# 06_-_MCU.net
KiCad netlist of a schematic drawn in Altium Designer
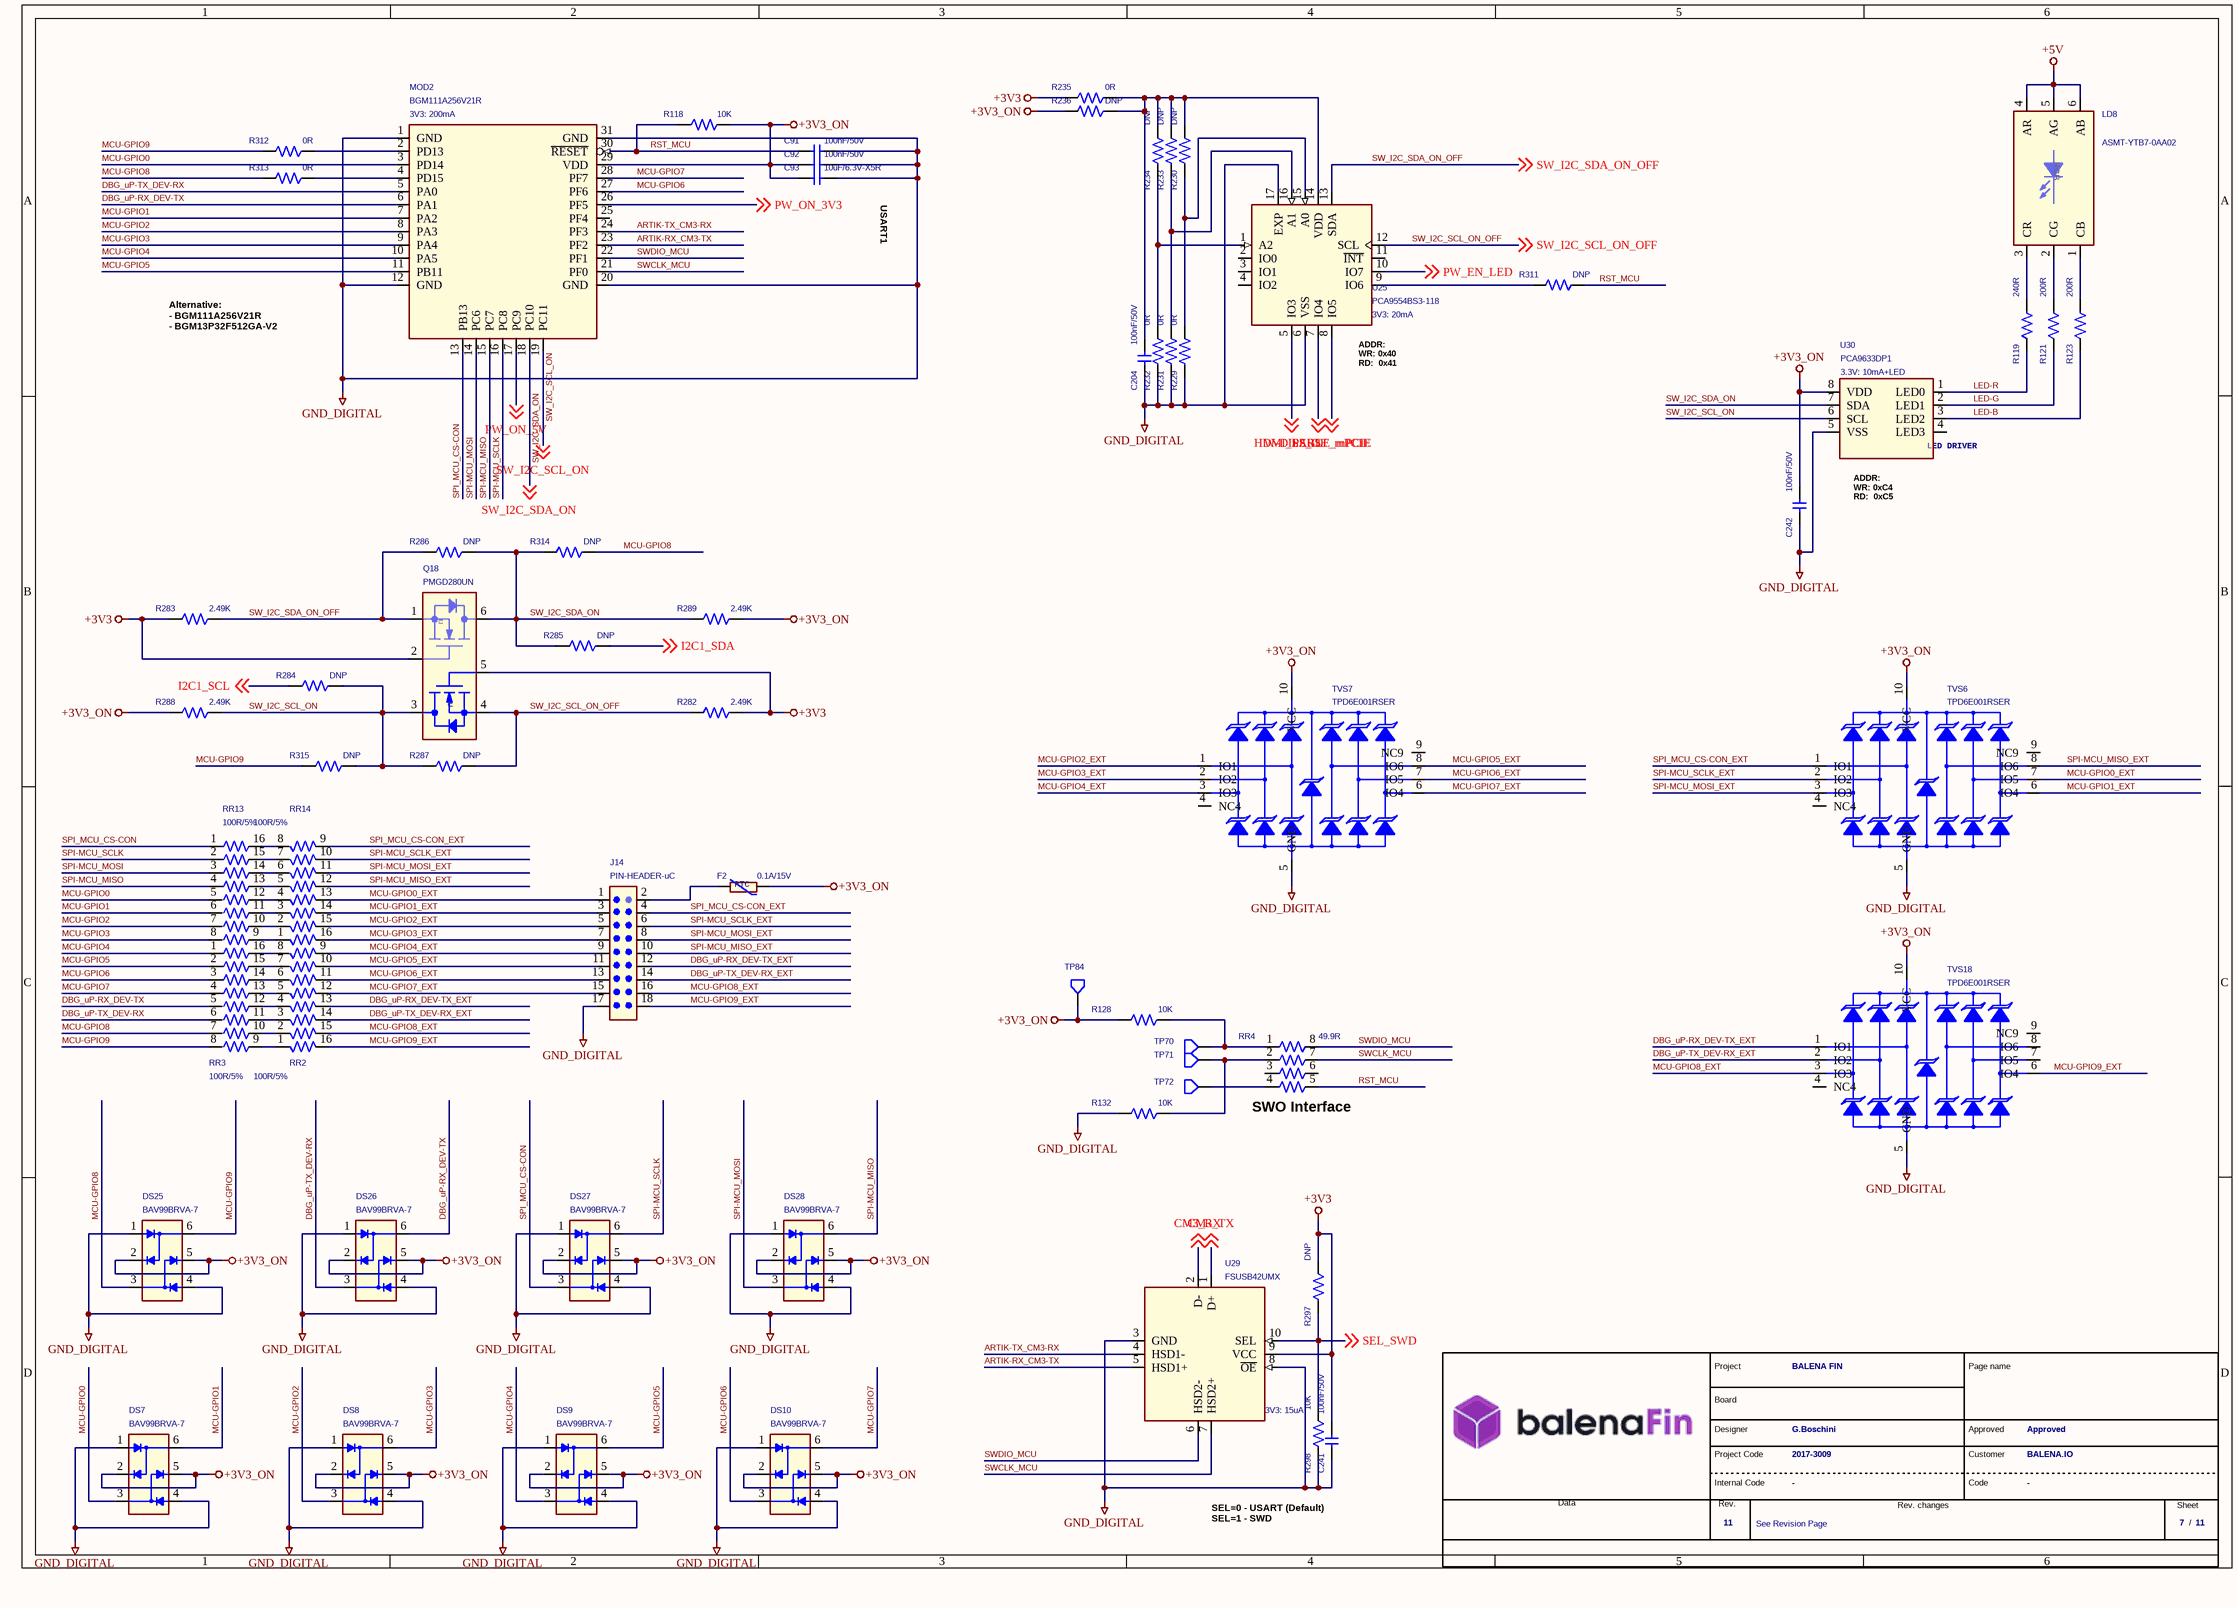
[diagram p0: 06 - MCU.SchDoc]

(export (version "E")
  (design (tool "Eeschema 10.0.6"))
  (components
    (comp (ref "C91")
      (value "100nF/50V")
      (footprint "CS-C-0402")
      (description "CHIP CAP.CER. 100nF 16V 10% X7R 0402")
      (fields (field (name "MPN") "Generic"))
      (libsource (lib "*") (part "CS-C-0402-100n/16V"))
    )
    (comp (ref "C92")
      (value "100nF/50V")
      (footprint "CS-C-0402")
      (description "CHIP CAP.CER. 100nF 16V 10% X7R 0402")
      (fields (field (name "MPN") "Generic"))
      (libsource (lib "*") (part "CS-C-0402-100n/16V"))
    )
    (comp (ref "C93")
      (value "10uF/6.3V-X5R")
      (footprint "CS-C-0402")
      (description "CHIP CAP.CER. 10uF 6.3V 20% X5R 0402")
      (fields (field (name "MPN") "Generic"))
      (libsource (lib "*") (part "CS-C-0402-10u/6V3-X5R"))
    )
    (comp (ref "C204")
      (value "100nF/50V")
      (footprint "CS-C-0402")
      (description "CHIP CAP.CER. 100nF 16V 10% X7R 0402")
      (fields (field (name "MPN") "Generic"))
      (libsource (lib "*") (part "CS-C-0402-100n/16V"))
    )
    (comp (ref "C241")
      (value "100nF/50V")
      (footprint "CS-C-0402")
      (description "CHIP CAP.CER. 100nF 16V 10% X7R 0402")
      (fields (field (name "MPN") "Generic"))
      (libsource (lib "*") (part "CS-C-0402-100n/16V"))
    )
    (comp (ref "C242")
      (value "100nF/50V")
      (footprint "CS-C-0402")
      (description "CHIP CAP.CER. 100nF 16V 10% X7R 0402")
      (fields (field (name "MPN") "Generic"))
      (libsource (lib "*") (part "CS-C-0402-100n/16V"))
    )
    (comp (ref "DS7")
      (value "BAV99BRVA-7")
      (footprint "SOT563")
      (description "Diode Switching 75V 0.215A 6-Pin SOT-563 T/R")
      (libsource (lib "*") (part "DIODO4x - BAV99BRVA-7 -0.2A/75V"))
    )
    (comp (ref "DS8")
      (value "BAV99BRVA-7")
      (footprint "SOT563")
      (description "Diode Switching 75V 0.215A 6-Pin SOT-563 T/R")
      (libsource (lib "*") (part "DIODO4x - BAV99BRVA-7 -0.2A/75V"))
    )
    (comp (ref "DS9")
      (value "BAV99BRVA-7")
      (footprint "SOT563")
      (description "Diode Switching 75V 0.215A 6-Pin SOT-563 T/R")
      (libsource (lib "*") (part "DIODO4x - BAV99BRVA-7 -0.2A/75V"))
    )
    (comp (ref "DS10")
      (value "BAV99BRVA-7")
      (footprint "SOT563")
      (description "Diode Switching 75V 0.215A 6-Pin SOT-563 T/R")
      (libsource (lib "*") (part "DIODO4x - BAV99BRVA-7 -0.2A/75V"))
    )
    (comp (ref "DS25")
      (value "BAV99BRVA-7")
      (footprint "SOT563")
      (description "Diode Switching 75V 0.215A 6-Pin SOT-563 T/R")
      (libsource (lib "*") (part "DIODO4x - BAV99BRVA-7 -0.2A/75V"))
    )
    (comp (ref "DS26")
      (value "BAV99BRVA-7")
      (footprint "SOT563")
      (description "Diode Switching 75V 0.215A 6-Pin SOT-563 T/R")
      (libsource (lib "*") (part "DIODO4x - BAV99BRVA-7 -0.2A/75V"))
    )
    (comp (ref "DS27")
      (value "BAV99BRVA-7")
      (footprint "SOT563")
      (description "Diode Switching 75V 0.215A 6-Pin SOT-563 T/R")
      (libsource (lib "*") (part "DIODO4x - BAV99BRVA-7 -0.2A/75V"))
    )
    (comp (ref "DS28")
      (value "BAV99BRVA-7")
      (footprint "SOT563")
      (description "Diode Switching 75V 0.215A 6-Pin SOT-563 T/R")
      (libsource (lib "*") (part "DIODO4x - BAV99BRVA-7 -0.2A/75V"))
    )
    (comp (ref "F2")
      (value "0.1A/15V")
      (footprint "FS-0603")
      (description "PTC RESET FUSE 15V 100MA 0603")
      (fields (field (name "MPN") "0ZCM0010FF2G"))
      (libsource (lib "*") (part "PTC - 0ZCM0010FF2G - 0.1A/15V"))
    )
    (comp (ref "J14")
      (value "PIN-HEADER-uC")
      (footprint "J-9X2-0254-MDT")
      (description "CONN HEADER THT 18POS 2.54MM DUAL ROW")
      (fields (field (name "MPN") "Generic"))
      (libsource (lib "*") (part "STRIP-J-9X2-0254-MDT"))
    )
    (comp (ref "LD8")
      (value "ASMT-YTB7-0AA02")
      (footprint "LD-PLCC6-GUIDAVLP")
      (description "LED RGB- 623nm Red, 529nm Green, PLCC6 469nm Blue LED Indication -  Discrete 2.1V Red, 3.1V")
      (libsource (lib "*") (part "LED RGB - ASMT-YTB7-0AA02"))
    )
    (comp (ref "MOD2")
      (value "BGM111A256V21R")
      (footprint "MOD-ARTIK-020")
      (description "Bluetooth v4.2 Transceiver Module 2.4GHz Integrated, Chip Surface Mount")
      (fields (field (name "POWER REQUIREMENTS") "3V3: 200mA"))
      (libsource (lib "*") (part "ARTIK - 020"))
    )
    (comp (ref "Q18")
      (value "PMGD280UN")
      (footprint "SOT363")
      (description "MOSFET 2N-CH 20V 0.87A 6TSSOP")
      (libsource (lib "*") (part "NMOS-2X - PMGD280UN - 0.87A/20V"))
    )
    (comp (ref "R118")
      (value "10K")
      (footprint "RS-0402")
      (description "CHIP RES. 10K 0402 1/16W 1%")
      (fields (field (name "MPN") "Generic"))
      (libsource (lib "*") (part "RS-0402-10k"))
    )
    (comp (ref "R119")
      (value "240R")
      (footprint "RS-0402")
      (description "CHIP RES. 240R 0402 1/16W 1% 100PPM/°C")
      (fields (field (name "MPN") "Generic"))
      (libsource (lib "*") (part "RS-0402-240r"))
    )
    (comp (ref "R121")
      (value "200R")
      (footprint "RS-0402")
      (description "CHIP RES. 200R 0402 1/16W 1% 100PPM/°C")
      (fields (field (name "MPN") "Generic"))
      (libsource (lib "*") (part "RS-0402-200r"))
    )
    (comp (ref "R123")
      (value "200R")
      (footprint "RS-0402")
      (description "CHIP RES. 200R 0402 1/16W 1% 100PPM/°C")
      (fields (field (name "MPN") "Generic"))
      (libsource (lib "*") (part "RS-0402-200r"))
    )
    (comp (ref "R128")
      (value "10K")
      (footprint "RS-0402")
      (description "CHIP RES. 10K 0402 1/16W 1%")
      (fields (field (name "MPN") "Generic"))
      (libsource (lib "*") (part "RS-0402-10k"))
    )
    (comp (ref "R132")
      (value "10K")
      (footprint "RS-0402")
      (description "CHIP RES. 10K 0402 1/16W 1%")
      (fields (field (name "MPN") "Generic"))
      (libsource (lib "*") (part "RS-0402-10k"))
    )
    (comp (ref "R229")
      (value "0R")
      (footprint "RS-0402")
      (description "CHIP RES. 0R 0402 1/16W 1%")
      (fields (field (name "MPN") "Generic"))
      (libsource (lib "*") (part "RS-0402-0r"))
    )
    (comp (ref "R230")
      (value "DNP")
      (footprint "RS-0402")
      (description "CHIP RES. 0402")
      (fields (field (name "MPN") "Generic"))
      (libsource (lib "*") (part "RS-0402"))
    )
    (comp (ref "R231")
      (value "0R")
      (footprint "RS-0402")
      (description "CHIP RES. 0R 0402 1/16W 1%")
      (fields (field (name "MPN") "Generic"))
      (libsource (lib "*") (part "RS-0402-0r"))
    )
    (comp (ref "R232")
      (value "0R")
      (footprint "RS-0402")
      (description "CHIP RES. 0R 0402 1/16W 1%")
      (fields (field (name "MPN") "Generic"))
      (libsource (lib "*") (part "RS-0402-0r"))
    )
    (comp (ref "R233")
      (value "DNP")
      (footprint "RS-0402")
      (description "CHIP RES. 0402")
      (fields (field (name "MPN") "Generic"))
      (libsource (lib "*") (part "RS-0402"))
    )
    (comp (ref "R234")
      (value "DNP")
      (footprint "RS-0402")
      (description "CHIP RES. 0402")
      (fields (field (name "MPN") "Generic"))
      (libsource (lib "*") (part "RS-0402"))
    )
    (comp (ref "R235")
      (value "0R")
      (footprint "RS-0402")
      (description "CHIP RES. 0R 0402 1/16W 1%")
      (fields (field (name "MPN") "Generic"))
      (libsource (lib "*") (part "RS-0402-0r"))
    )
    (comp (ref "R236")
      (value "DNP")
      (footprint "RS-0402")
      (description "CHIP RES. 0402")
      (fields (field (name "MPN") "Generic"))
      (libsource (lib "*") (part "RS-0402"))
    )
    (comp (ref "R282")
      (value "2.49K")
      (footprint "RS-0402")
      (description "CHIP RES. 2K49 0402 1/16W 1% 100PPM/°C")
      (fields (field (name "MPN") "Generic"))
      (libsource (lib "*") (part "RS-0402-2.49k"))
    )
    (comp (ref "R283")
      (value "2.49K")
      (footprint "RS-0402")
      (description "CHIP RES. 2K49 0402 1/16W 1% 100PPM/°C")
      (fields (field (name "MPN") "Generic"))
      (libsource (lib "*") (part "RS-0402-2.49k"))
    )
    (comp (ref "R284")
      (value "DNP")
      (footprint "RS-0402")
      (description "CHIP RES. 0402")
      (fields (field (name "MPN") "Generic"))
      (libsource (lib "*") (part "RS-0402"))
    )
    (comp (ref "R285")
      (value "DNP")
      (footprint "RS-0402")
      (description "CHIP RES. 0402")
      (fields (field (name "MPN") "Generic"))
      (libsource (lib "*") (part "RS-0402"))
    )
    (comp (ref "R286")
      (value "DNP")
      (footprint "RS-0402")
      (description "CHIP RES. 0R 0402 1/10W 1%")
      (fields (field (name "MPN") "Generic"))
      (libsource (lib "*") (part "RS-0402"))
    )
    (comp (ref "R287")
      (value "DNP")
      (footprint "RS-0402")
      (description "CHIP RES. 0R 0402 1/10W 1%")
      (fields (field (name "MPN") "Generic"))
      (libsource (lib "*") (part "RS-0402"))
    )
    (comp (ref "R288")
      (value "2.49K")
      (footprint "RS-0402")
      (description "CHIP RES. 2K49 0402 1/16W 1% 100PPM/°C")
      (fields (field (name "MPN") "Generic"))
      (libsource (lib "*") (part "RS-0402-2.49k"))
    )
    (comp (ref "R289")
      (value "2.49K")
      (footprint "RS-0402")
      (description "CHIP RES. 2K49 0402 1/16W 1% 100PPM/°C")
      (fields (field (name "MPN") "Generic"))
      (libsource (lib "*") (part "RS-0402-2.49k"))
    )
    (comp (ref "R297")
      (value "DNP")
      (footprint "RS-0402")
      (description "CHIP RES. 0402")
      (fields (field (name "MPN") "Generic"))
      (libsource (lib "*") (part "RS-0402"))
    )
    (comp (ref "R298")
      (value "10K")
      (footprint "RS-0402")
      (description "CHIP RES. 10K 0402 1/16W 1%")
      (fields (field (name "MPN") "Generic"))
      (libsource (lib "*") (part "RS-0402-10k"))
    )
    (comp (ref "R311")
      (value "DNP")
      (footprint "RS-0402")
      (description "CHIP RES. 0R 0402 1/16W 1%")
      (fields (field (name "MPN") "Generic"))
      (libsource (lib "*") (part "RS-0402-0r"))
    )
    (comp (ref "R312")
      (value "0R")
      (footprint "RS-0402")
      (description "CHIP RES. 0R 0402 1/16W 1%")
      (fields (field (name "MPN") "Generic"))
      (libsource (lib "*") (part "RS-0402-0r"))
    )
    (comp (ref "R313")
      (value "0R")
      (footprint "RS-0402")
      (description "CHIP RES. 0R 0402 1/16W 1%")
      (fields (field (name "MPN") "Generic"))
      (libsource (lib "*") (part "RS-0402-0r"))
    )
    (comp (ref "R314")
      (value "DNP")
      (footprint "RS-0402")
      (description "CHIP RES. 0402")
      (fields (field (name "MPN") "Generic"))
      (libsource (lib "*") (part "RS-0402"))
    )
    (comp (ref "R315")
      (value "DNP")
      (footprint "RS-0402")
      (description "CHIP RES. 0402")
      (fields (field (name "MPN") "Generic"))
      (libsource (lib "*") (part "RS-0402"))
    )
    (comp (ref "RR2")
      (value "100R/5%")
      (footprint "RR-8X-1506")
      (description "RES ARRAY 8 RES 100 OHM 1506 5%")
      (fields (field (name "MPN") "Generic"))
      (libsource (lib "*") (part "RR-8X-1506-100r/5%"))
    )
    (comp (ref "RR3")
      (value "100R/5%")
      (footprint "RR-8X-1506")
      (description "RES ARRAY 8 RES 100 OHM 1506 5%")
      (fields (field (name "MPN") "Generic"))
      (libsource (lib "*") (part "RR-8X-1506-100r/5%"))
    )
    (comp (ref "RR4")
      (value "49.9R")
      (footprint "RR-1206")
      (description "RES ARRAY 4 RES 49.9 OHM 1206 1%")
      (fields (field (name "MPN") "Generic"))
      (libsource (lib "*") (part "RR-1206-49.9r"))
    )
    (comp (ref "RR13")
      (value "100R/5%")
      (footprint "RR-8X-1506")
      (description "RES ARRAY 8 RES 100 OHM 1506 5%")
      (fields (field (name "MPN") "Generic"))
      (libsource (lib "*") (part "RR-8X-1506-100r/5%"))
    )
    (comp (ref "RR14")
      (value "100R/5%")
      (footprint "RR-8X-1506")
      (description "RES ARRAY 8 RES 100 OHM 1506 5%")
      (fields (field (name "MPN") "Generic"))
      (libsource (lib "*") (part "RR-8X-1506-100r/5%"))
    )
    (comp (ref "TP70")
      (value "TPS")
      (footprint "TPS-0100")
      (description "TEST POINT SMD")
      (fields (field (name "MPN") "TP-No-BoM"))
      (libsource (lib "*") (part "TEST POINT SMD 1 MM"))
    )
    (comp (ref "TP71")
      (value "TPS")
      (footprint "TPS-0100")
      (description "TEST POINT SMD")
      (fields (field (name "MPN") "TP-No-BoM"))
      (libsource (lib "*") (part "TEST POINT SMD 1 MM"))
    )
    (comp (ref "TP72")
      (value "TPS")
      (footprint "TPS-0100")
      (description "TEST POINT SMD")
      (fields (field (name "MPN") "TP-No-BoM"))
      (libsource (lib "*") (part "TEST POINT SMD 1 MM"))
    )
    (comp (ref "TP84")
      (value "TPS")
      (footprint "TPS-0100")
      (description "TEST POINT SMD")
      (fields (field (name "MPN") "TP-No-BoM"))
      (libsource (lib "*") (part "TEST POINT SMD 1 MM"))
    )
    (comp (ref "TVS6")
      (value "TPD6E001RSER")
      (footprint "UFQFN10")
      (description "TVS DIODE 5VWM")
      (libsource (lib "*") (part "TVS-UNI6x - TPD6E001RSER"))
    )
    (comp (ref "TVS7")
      (value "TPD6E001RSER")
      (footprint "UFQFN10")
      (description "TVS DIODE 5VWM")
      (libsource (lib "*") (part "TVS-UNI6x - TPD6E001RSER"))
    )
    (comp (ref "TVS18")
      (value "TPD6E001RSER")
      (footprint "UFQFN10")
      (description "TVS DIODE 5VWM")
      (libsource (lib "*") (part "TVS-UNI6x - TPD6E001RSER"))
    )
    (comp (ref "U25")
      (value "PCA9554BS3-118")
      (footprint "QFN16-EXP-3X3-4X4")
      (description "IC I/O EXPANDER I2C 8B 16HVQFN")
      (fields (field (name "POWER REQUIREMENTS") "3V3: 20mA"))
      (libsource (lib "*") (part "IO EXP-8b - PCA9554BS3-118"))
    )
    (comp (ref "U29")
      (value "FSUSB42UMX")
      (footprint "UMLP10")
      (description "USB Switch IC 1 Channel 10-UMLP (1.8x1.4)")
      (fields (field (name "POWER REQUIREMENTS") "3V3: 15uA"))
      (libsource (lib "*") (part "SWITCH-USB - FSUSB42UMX"))
    )
    (comp (ref "U30")
      (value "PCA9633DP1")
      (footprint "MSOP8")
      (description "IC LED DRIVER PS DIM 25MA 8TSSOP")
      (fields (field (name "POWER REQUIREMENTS") "3.3V: 10mA+LED"))
      (libsource (lib "*") (part "LED DRIVER-4x - PCA9633DP1"))
    )
  )
  (nets
    (net (code "1") (name "+3V3") (class "Default")
      (node (ref "C241") (pin "1") (pinfunction "1_1") (pintype "passive"))
      (node (ref "Q18") (pin "2") (pinfunction "G1_2") (pintype "passive"))
      (node (ref "Q18") (pin "5") (pinfunction "G2_5") (pintype "passive"))
      (node (ref "R235") (pin "2") (pinfunction "2_2") (pintype "passive"))
      (node (ref "R282") (pin "1") (pinfunction "1_1") (pintype "passive"))
      (node (ref "R283") (pin "2") (pinfunction "2_2") (pintype "passive"))
      (node (ref "R297") (pin "2") (pinfunction "2_2") (pintype "passive"))
      (node (ref "U29") (pin "9") (pinfunction "VCC_9") (pintype "power_in"))
    )
    (net (code "2") (name "+3V3_ON") (class "Default")
      (node (ref "C242") (pin "1") (pinfunction "1_1") (pintype "passive"))
      (node (ref "C92") (pin "1") (pinfunction "1_1") (pintype "passive"))
      (node (ref "C93") (pin "1") (pinfunction "1_1") (pintype "passive"))
      (node (ref "DS10") (pin "2") (pinfunction "C1_2") (pintype "passive"))
      (node (ref "DS10") (pin "5") (pinfunction "C2_5") (pintype "passive"))
      (node (ref "DS25") (pin "2") (pinfunction "C1_2") (pintype "passive"))
      (node (ref "DS25") (pin "5") (pinfunction "C2_5") (pintype "passive"))
      (node (ref "DS26") (pin "2") (pinfunction "C1_2") (pintype "passive"))
      (node (ref "DS26") (pin "5") (pinfunction "C2_5") (pintype "passive"))
      (node (ref "DS27") (pin "2") (pinfunction "C1_2") (pintype "passive"))
      (node (ref "DS27") (pin "5") (pinfunction "C2_5") (pintype "passive"))
      (node (ref "DS28") (pin "2") (pinfunction "C1_2") (pintype "passive"))
      (node (ref "DS28") (pin "5") (pinfunction "C2_5") (pintype "passive"))
      (node (ref "DS7") (pin "2") (pinfunction "C1_2") (pintype "passive"))
      (node (ref "DS7") (pin "5") (pinfunction "C2_5") (pintype "passive"))
      (node (ref "DS8") (pin "2") (pinfunction "C1_2") (pintype "passive"))
      (node (ref "DS8") (pin "5") (pinfunction "C2_5") (pintype "passive"))
      (node (ref "DS9") (pin "2") (pinfunction "C1_2") (pintype "passive"))
      (node (ref "DS9") (pin "5") (pinfunction "C2_5") (pintype "passive"))
      (node (ref "F2") (pin "2") (pinfunction "2_2") (pintype "passive"))
      (node (ref "MOD2") (pin "29") (pinfunction "VDD_29") (pintype "power_in"))
      (node (ref "R118") (pin "2") (pinfunction "2_2") (pintype "passive"))
      (node (ref "R128") (pin "2") (pinfunction "2_2") (pintype "passive"))
      (node (ref "R236") (pin "2") (pinfunction "2_2") (pintype "passive"))
      (node (ref "R288") (pin "2") (pinfunction "2_2") (pintype "passive"))
      (node (ref "R289") (pin "1") (pinfunction "1_1") (pintype "passive"))
      (node (ref "TP84") (pin "1") (pinfunction "TP_1") (pintype "passive"))
      (node (ref "TVS18") (pin "10") (pinfunction "VCC_10") (pintype "passive"))
      (node (ref "TVS6") (pin "10") (pinfunction "VCC_10") (pintype "passive"))
      (node (ref "TVS7") (pin "10") (pinfunction "VCC_10") (pintype "passive"))
      (node (ref "U30") (pin "8") (pinfunction "VDD_8") (pintype "power_in"))
    )
    (net (code "3") (name "+5V") (class "Default")
      (node (ref "LD8") (pin "4") (pinfunction "AR_4") (pintype "passive"))
      (node (ref "LD8") (pin "5") (pinfunction "AG_5") (pintype "passive"))
      (node (ref "LD8") (pin "6") (pinfunction "AB_6") (pintype "passive"))
    )
    (net (code "4") (name "/ARTIK-RX_CM3-TX") (class "Default")
      (node (ref "MOD2") (pin "23") (pinfunction "PF2_23") (pintype "bidirectional"))
      (node (ref "U29") (pin "5") (pinfunction "HSD1+_5") (pintype "bidirectional"))
    )
    (net (code "5") (name "/ARTIK-TX_CM3-RX") (class "Default")
      (node (ref "MOD2") (pin "24") (pinfunction "PF3_24") (pintype "bidirectional"))
      (node (ref "U29") (pin "4") (pinfunction "HSD1-_4") (pintype "bidirectional"))
    )
    (net (code "6") (name "/DBG_uP-RX_DEV-TX") (class "Default")
      (node (ref "DS26") (pin "6") (pinfunction "AC1_6") (pintype "passive"))
      (node (ref "MOD2") (pin "6") (pinfunction "PA1_6") (pintype "bidirectional"))
      (node (ref "RR3") (pin "5") (pinfunction "5_5") (pintype "passive"))
    )
    (net (code "7") (name "/DBG_uP-RX_DEV-TX_EXT") (class "Default")
      (node (ref "J14") (pin "12") (pinfunction "12_12") (pintype "passive"))
      (node (ref "RR2") (pin "13") (pinfunction "13_13") (pintype "passive"))
      (node (ref "TVS18") (pin "1") (pinfunction "IO1_1") (pintype "passive"))
    )
    (net (code "8") (name "/DBG_uP-TX_DEV-RX") (class "Default")
      (node (ref "DS26") (pin "3") (pinfunction "AC2_3") (pintype "passive"))
      (node (ref "MOD2") (pin "5") (pinfunction "PA0_5") (pintype "bidirectional"))
      (node (ref "RR3") (pin "6") (pinfunction "6_6") (pintype "passive"))
    )
    (net (code "9") (name "/DBG_uP-TX_DEV-RX_EXT") (class "Default")
      (node (ref "J14") (pin "14") (pinfunction "14_14") (pintype "passive"))
      (node (ref "RR2") (pin "14") (pinfunction "14_14") (pintype "passive"))
      (node (ref "TVS18") (pin "2") (pinfunction "IO2_2") (pintype "passive"))
    )
    (net (code "10") (name "/LED-B") (class "Default")
      (node (ref "R123") (pin "2") (pinfunction "2_2") (pintype "passive"))
      (node (ref "U30") (pin "3") (pinfunction "LED2_3") (pintype "open_collector"))
    )
    (net (code "11") (name "/LED-G") (class "Default")
      (node (ref "R121") (pin "2") (pinfunction "2_2") (pintype "passive"))
      (node (ref "U30") (pin "2") (pinfunction "LED1_2") (pintype "open_collector"))
    )
    (net (code "12") (name "/LED-R") (class "Default")
      (node (ref "R119") (pin "2") (pinfunction "2_2") (pintype "passive"))
      (node (ref "U30") (pin "1") (pinfunction "LED0_1") (pintype "open_collector"))
    )
    (net (code "13") (name "/MCU-GPIO0") (class "Default")
      (node (ref "DS7") (pin "3") (pinfunction "AC2_3") (pintype "passive"))
      (node (ref "MOD2") (pin "3") (pinfunction "PD14_3") (pintype "bidirectional"))
      (node (ref "RR13") (pin "5") (pinfunction "5_5") (pintype "passive"))
    )
    (net (code "14") (name "/MCU-GPIO0_EXT") (class "Default")
      (node (ref "J14") (pin "1") (pinfunction "1_1") (pintype "passive"))
      (node (ref "RR14") (pin "13") (pinfunction "13_13") (pintype "passive"))
      (node (ref "TVS6") (pin "7") (pinfunction "IO5_7") (pintype "passive"))
    )
    (net (code "15") (name "/MCU-GPIO1") (class "Default")
      (node (ref "DS7") (pin "6") (pinfunction "AC1_6") (pintype "passive"))
      (node (ref "MOD2") (pin "7") (pinfunction "PA2_7") (pintype "bidirectional"))
      (node (ref "RR13") (pin "6") (pinfunction "6_6") (pintype "passive"))
    )
    (net (code "16") (name "/MCU-GPIO1_EXT") (class "Default")
      (node (ref "J14") (pin "3") (pinfunction "3_3") (pintype "passive"))
      (node (ref "RR14") (pin "14") (pinfunction "14_14") (pintype "passive"))
      (node (ref "TVS6") (pin "6") (pinfunction "IO4_6") (pintype "passive"))
    )
    (net (code "17") (name "/MCU-GPIO2") (class "Default")
      (node (ref "DS8") (pin "3") (pinfunction "AC2_3") (pintype "passive"))
      (node (ref "MOD2") (pin "8") (pinfunction "PA3_8") (pintype "bidirectional"))
      (node (ref "RR13") (pin "7") (pinfunction "7_7") (pintype "passive"))
    )
    (net (code "18") (name "/MCU-GPIO2_EXT") (class "Default")
      (node (ref "J14") (pin "5") (pinfunction "5_5") (pintype "passive"))
      (node (ref "RR14") (pin "15") (pinfunction "15_15") (pintype "passive"))
      (node (ref "TVS7") (pin "1") (pinfunction "IO1_1") (pintype "passive"))
    )
    (net (code "19") (name "/MCU-GPIO3") (class "Default")
      (node (ref "DS8") (pin "6") (pinfunction "AC1_6") (pintype "passive"))
      (node (ref "MOD2") (pin "9") (pinfunction "PA4_9") (pintype "bidirectional"))
      (node (ref "RR13") (pin "8") (pinfunction "8_8") (pintype "passive"))
    )
    (net (code "20") (name "/MCU-GPIO3_EXT") (class "Default")
      (node (ref "J14") (pin "7") (pinfunction "7_7") (pintype "passive"))
      (node (ref "RR14") (pin "16") (pinfunction "16_16") (pintype "passive"))
      (node (ref "TVS7") (pin "2") (pinfunction "IO2_2") (pintype "passive"))
    )
    (net (code "21") (name "/MCU-GPIO4") (class "Default")
      (node (ref "DS9") (pin "3") (pinfunction "AC2_3") (pintype "passive"))
      (node (ref "MOD2") (pin "10") (pinfunction "PA5_10") (pintype "bidirectional"))
      (node (ref "RR3") (pin "1") (pinfunction "1_1") (pintype "passive"))
    )
    (net (code "22") (name "/MCU-GPIO4_EXT") (class "Default")
      (node (ref "J14") (pin "9") (pinfunction "9_9") (pintype "passive"))
      (node (ref "RR2") (pin "9") (pinfunction "9_9") (pintype "passive"))
      (node (ref "TVS7") (pin "3") (pinfunction "IO3_3") (pintype "passive"))
    )
    (net (code "23") (name "/MCU-GPIO5") (class "Default")
      (node (ref "DS9") (pin "6") (pinfunction "AC1_6") (pintype "passive"))
      (node (ref "MOD2") (pin "11") (pinfunction "PB11_11") (pintype "bidirectional"))
      (node (ref "RR3") (pin "2") (pinfunction "2_2") (pintype "passive"))
    )
    (net (code "24") (name "/MCU-GPIO5_EXT") (class "Default")
      (node (ref "J14") (pin "11") (pinfunction "11_11") (pintype "passive"))
      (node (ref "RR2") (pin "10") (pinfunction "10_10") (pintype "passive"))
      (node (ref "TVS7") (pin "8") (pinfunction "IO6_8") (pintype "passive"))
    )
    (net (code "25") (name "/MCU-GPIO6") (class "Default")
      (node (ref "DS10") (pin "3") (pinfunction "AC2_3") (pintype "passive"))
      (node (ref "MOD2") (pin "27") (pinfunction "PF6_27") (pintype "bidirectional"))
      (node (ref "RR3") (pin "3") (pinfunction "3_3") (pintype "passive"))
    )
    (net (code "26") (name "/MCU-GPIO6_EXT") (class "Default")
      (node (ref "J14") (pin "13") (pinfunction "13_13") (pintype "passive"))
      (node (ref "RR2") (pin "11") (pinfunction "11_11") (pintype "passive"))
      (node (ref "TVS7") (pin "7") (pinfunction "IO5_7") (pintype "passive"))
    )
    (net (code "27") (name "/MCU-GPIO7") (class "Default")
      (node (ref "DS10") (pin "6") (pinfunction "AC1_6") (pintype "passive"))
      (node (ref "MOD2") (pin "28") (pinfunction "PF7_28") (pintype "bidirectional"))
      (node (ref "RR3") (pin "4") (pinfunction "4_4") (pintype "passive"))
    )
    (net (code "28") (name "/MCU-GPIO7_EXT") (class "Default")
      (node (ref "J14") (pin "15") (pinfunction "15_15") (pintype "passive"))
      (node (ref "RR2") (pin "12") (pinfunction "12_12") (pintype "passive"))
      (node (ref "TVS7") (pin "6") (pinfunction "IO4_6") (pintype "passive"))
    )
    (net (code "29") (name "/MCU-GPIO8") (class "Default")
      (node (ref "DS25") (pin "3") (pinfunction "AC2_3") (pintype "passive"))
      (node (ref "R313") (pin "2") (pinfunction "2_2") (pintype "passive"))
      (node (ref "R314") (pin "1") (pinfunction "1_1") (pintype "passive"))
      (node (ref "RR3") (pin "7") (pinfunction "7_7") (pintype "passive"))
    )
    (net (code "30") (name "/MCU-GPIO8_EXT") (class "Default")
      (node (ref "J14") (pin "16") (pinfunction "16_16") (pintype "passive"))
      (node (ref "RR2") (pin "15") (pinfunction "15_15") (pintype "passive"))
      (node (ref "TVS18") (pin "3") (pinfunction "IO3_3") (pintype "passive"))
    )
    (net (code "31") (name "/MCU-GPIO9") (class "Default")
      (node (ref "DS25") (pin "6") (pinfunction "AC1_6") (pintype "passive"))
      (node (ref "R312") (pin "2") (pinfunction "2_2") (pintype "passive"))
      (node (ref "R315") (pin "2") (pinfunction "2_2") (pintype "passive"))
      (node (ref "RR3") (pin "8") (pinfunction "8_8") (pintype "passive"))
    )
    (net (code "32") (name "/MCU-GPIO9_EXT") (class "Default")
      (node (ref "J14") (pin "18") (pinfunction "18_18") (pintype "passive"))
      (node (ref "RR2") (pin "16") (pinfunction "16_16") (pintype "passive"))
      (node (ref "TVS18") (pin "6") (pinfunction "IO4_6") (pintype "passive"))
    )
    (net (code "33") (name "/RST_MCU") (class "Default")
      (node (ref "C91") (pin "1") (pinfunction "1_1") (pintype "passive"))
      (node (ref "MOD2") (pin "30") (pinfunction "~{RESET}_30") (pintype "input"))
      (node (ref "R118") (pin "1") (pinfunction "1_1") (pintype "passive"))
      (node (ref "R311") (pin "1") (pinfunction "1_1") (pintype "passive"))
      (node (ref "RR4") (pin "5") (pinfunction "5_5") (pintype "passive"))
    )
    (net (code "34") (name "/SPI-MCU_MISO") (class "Default")
      (node (ref "DS28") (pin "6") (pinfunction "AC1_6") (pintype "passive"))
      (node (ref "MOD2") (pin "15") (pinfunction "PC7_15") (pintype "bidirectional"))
      (node (ref "RR13") (pin "4") (pinfunction "4_4") (pintype "passive"))
    )
    (net (code "35") (name "/SPI-MCU_MISO_EXT") (class "Default")
      (node (ref "J14") (pin "10") (pinfunction "10_10") (pintype "passive"))
      (node (ref "RR14") (pin "12") (pinfunction "12_12") (pintype "passive"))
      (node (ref "TVS6") (pin "8") (pinfunction "IO6_8") (pintype "passive"))
    )
    (net (code "36") (name "/SPI-MCU_MOSI") (class "Default")
      (node (ref "DS28") (pin "3") (pinfunction "AC2_3") (pintype "passive"))
      (node (ref "MOD2") (pin "14") (pinfunction "PC6_14") (pintype "bidirectional"))
      (node (ref "RR13") (pin "3") (pinfunction "3_3") (pintype "passive"))
    )
    (net (code "37") (name "/SPI-MCU_MOSI_EXT") (class "Default")
      (node (ref "J14") (pin "8") (pinfunction "8_8") (pintype "passive"))
      (node (ref "RR14") (pin "11") (pinfunction "11_11") (pintype "passive"))
      (node (ref "TVS6") (pin "3") (pinfunction "IO3_3") (pintype "passive"))
    )
    (net (code "38") (name "/SPI-MCU_SCLK") (class "Default")
      (node (ref "DS27") (pin "6") (pinfunction "AC1_6") (pintype "passive"))
      (node (ref "MOD2") (pin "16") (pinfunction "PC8_16") (pintype "bidirectional"))
      (node (ref "RR13") (pin "2") (pinfunction "2_2") (pintype "passive"))
    )
    (net (code "39") (name "/SPI-MCU_SCLK_EXT") (class "Default")
      (node (ref "J14") (pin "6") (pinfunction "6_6") (pintype "passive"))
      (node (ref "RR14") (pin "10") (pinfunction "10_10") (pintype "passive"))
      (node (ref "TVS6") (pin "2") (pinfunction "IO2_2") (pintype "passive"))
    )
    (net (code "40") (name "/SPI_MCU_CS-CON") (class "Default")
      (node (ref "DS27") (pin "3") (pinfunction "AC2_3") (pintype "passive"))
      (node (ref "MOD2") (pin "13") (pinfunction "PB13_13") (pintype "bidirectional"))
      (node (ref "RR13") (pin "1") (pinfunction "1_1") (pintype "passive"))
    )
    (net (code "41") (name "/SPI_MCU_CS-CON_EXT") (class "Default")
      (node (ref "J14") (pin "4") (pinfunction "4_4") (pintype "passive"))
      (node (ref "RR14") (pin "9") (pinfunction "9_9") (pintype "passive"))
      (node (ref "TVS6") (pin "1") (pinfunction "IO1_1") (pintype "passive"))
    )
    (net (code "42") (name "/SWCLK_MCU") (class "Default")
      (node (ref "MOD2") (pin "21") (pinfunction "PF0_21") (pintype "bidirectional"))
      (node (ref "RR4") (pin "7") (pinfunction "7_7") (pintype "passive"))
      (node (ref "U29") (pin "7") (pinfunction "HSD2+_7") (pintype "bidirectional"))
    )
    (net (code "43") (name "/SWDIO_MCU") (class "Default")
      (node (ref "MOD2") (pin "22") (pinfunction "PF1_22") (pintype "bidirectional"))
      (node (ref "RR4") (pin "8") (pinfunction "8_8") (pintype "passive"))
      (node (ref "U29") (pin "6") (pinfunction "HSD2-_6") (pintype "bidirectional"))
    )
    (net (code "44") (name "CM3_RX") (class "Default")
      (node (ref "U29") (pin "2") (pinfunction "D-_2") (pintype "bidirectional"))
    )
    (net (code "45") (name "CM3_TX") (class "Default")
      (node (ref "U29") (pin "1") (pinfunction "D+_1") (pintype "bidirectional"))
    )
    (net (code "46") (name "GND_DIGITAL") (class "Default")
      (node (ref "C204") (pin "2") (pinfunction "2_2") (pintype "passive"))
      (node (ref "C241") (pin "2") (pinfunction "2_2") (pintype "passive"))
      (node (ref "C242") (pin "2") (pinfunction "2_2") (pintype "passive"))
      (node (ref "C91") (pin "2") (pinfunction "2_2") (pintype "passive"))
      (node (ref "C92") (pin "2") (pinfunction "2_2") (pintype "passive"))
      (node (ref "C93") (pin "2") (pinfunction "2_2") (pintype "passive"))
      (node (ref "DS10") (pin "1") (pinfunction "A1_1") (pintype "passive"))
      (node (ref "DS10") (pin "4") (pinfunction "A2_4") (pintype "passive"))
      (node (ref "DS25") (pin "1") (pinfunction "A1_1") (pintype "passive"))
      (node (ref "DS25") (pin "4") (pinfunction "A2_4") (pintype "passive"))
      (node (ref "DS26") (pin "1") (pinfunction "A1_1") (pintype "passive"))
      (node (ref "DS26") (pin "4") (pinfunction "A2_4") (pintype "passive"))
      (node (ref "DS27") (pin "1") (pinfunction "A1_1") (pintype "passive"))
      (node (ref "DS27") (pin "4") (pinfunction "A2_4") (pintype "passive"))
      (node (ref "DS28") (pin "1") (pinfunction "A1_1") (pintype "passive"))
      (node (ref "DS28") (pin "4") (pinfunction "A2_4") (pintype "passive"))
      (node (ref "DS7") (pin "1") (pinfunction "A1_1") (pintype "passive"))
      (node (ref "DS7") (pin "4") (pinfunction "A2_4") (pintype "passive"))
      (node (ref "DS8") (pin "1") (pinfunction "A1_1") (pintype "passive"))
      (node (ref "DS8") (pin "4") (pinfunction "A2_4") (pintype "passive"))
      (node (ref "DS9") (pin "1") (pinfunction "A1_1") (pintype "passive"))
      (node (ref "DS9") (pin "4") (pinfunction "A2_4") (pintype "passive"))
      (node (ref "J14") (pin "17") (pinfunction "17_17") (pintype "passive"))
      (node (ref "MOD2") (pin "1") (pinfunction "GND_1") (pintype "power_in"))
      (node (ref "MOD2") (pin "12") (pinfunction "GND_12") (pintype "power_in"))
      (node (ref "MOD2") (pin "20") (pinfunction "GND_20") (pintype "power_in"))
      (node (ref "MOD2") (pin "31") (pinfunction "GND_31") (pintype "power_in"))
      (node (ref "R132") (pin "2") (pinfunction "2_2") (pintype "passive"))
      (node (ref "R229") (pin "1") (pinfunction "1_1") (pintype "passive"))
      (node (ref "R231") (pin "1") (pinfunction "1_1") (pintype "passive"))
      (node (ref "R232") (pin "1") (pinfunction "1_1") (pintype "passive"))
      (node (ref "R298") (pin "1") (pinfunction "1_1") (pintype "passive"))
      (node (ref "TVS18") (pin "5") (pinfunction "GND_5") (pintype "power_in"))
      (node (ref "TVS6") (pin "5") (pinfunction "GND_5") (pintype "power_in"))
      (node (ref "TVS7") (pin "5") (pinfunction "GND_5") (pintype "power_in"))
      (node (ref "U25") (pin "17") (pinfunction "EXP_17") (pintype "power_in"))
      (node (ref "U25") (pin "6") (pinfunction "VSS_6") (pintype "power_in"))
      (node (ref "U29") (pin "3") (pinfunction "GND_3") (pintype "power_in"))
      (node (ref "U29") (pin "8") (pinfunction "~{OE}_8") (pintype "input"))
      (node (ref "U30") (pin "5") (pinfunction "VSS_5") (pintype "power_in"))
    )
    (net (code "47") (name "HDMI_LS_OE") (class "Default")
      (node (ref "U25") (pin "5") (pinfunction "IO3_5") (pintype "bidirectional"))
    )
    (net (code "48") (name "I2C1_SCL") (class "Default")
      (node (ref "R284") (pin "2") (pinfunction "2_2") (pintype "passive"))
    )
    (net (code "49") (name "I2C1_SDA") (class "Default")
      (node (ref "R285") (pin "1") (pinfunction "1_1") (pintype "passive"))
    )
    (net (code "50") (name "Net-(F2-Pad1)") (class "Default")
      (node (ref "F2") (pin "1") (pinfunction "1_1") (pintype "passive"))
      (node (ref "J14") (pin "2") (pinfunction "2_2") (pintype "passive"))
    )
    (net (code "51") (name "Net-(LD8-CB)") (class "Default")
      (node (ref "LD8") (pin "1") (pinfunction "CB_1") (pintype "passive"))
      (node (ref "R123") (pin "1") (pinfunction "1_1") (pintype "passive"))
    )
    (net (code "52") (name "Net-(LD8-CG)") (class "Default")
      (node (ref "LD8") (pin "2") (pinfunction "CG_2") (pintype "passive"))
      (node (ref "R121") (pin "1") (pinfunction "1_1") (pintype "passive"))
    )
    (net (code "53") (name "Net-(LD8-CR)") (class "Default")
      (node (ref "LD8") (pin "3") (pinfunction "CR_3") (pintype "passive"))
      (node (ref "R119") (pin "1") (pinfunction "1_1") (pintype "passive"))
    )
    (net (code "54") (name "Net-(MOD2-PD13)") (class "Default")
      (node (ref "MOD2") (pin "2") (pinfunction "PD13_2") (pintype "bidirectional"))
      (node (ref "R312") (pin "1") (pinfunction "1_1") (pintype "passive"))
    )
    (net (code "55") (name "Net-(MOD2-PD15)") (class "Default")
      (node (ref "MOD2") (pin "4") (pinfunction "PD15_4") (pintype "bidirectional"))
      (node (ref "R313") (pin "1") (pinfunction "1_1") (pintype "passive"))
    )
    (net (code "56") (name "Net-(RR2-Pad1)") (class "Default")
      (node (ref "RR2") (pin "1") (pinfunction "1_1") (pintype "passive"))
      (node (ref "RR3") (pin "9") (pinfunction "9_9") (pintype "passive"))
    )
    (net (code "57") (name "Net-(RR2-Pad2)") (class "Default")
      (node (ref "RR2") (pin "2") (pinfunction "2_2") (pintype "passive"))
      (node (ref "RR3") (pin "10") (pinfunction "10_10") (pintype "passive"))
    )
    (net (code "58") (name "Net-(RR2-Pad3)") (class "Default")
      (node (ref "RR2") (pin "3") (pinfunction "3_3") (pintype "passive"))
      (node (ref "RR3") (pin "11") (pinfunction "11_11") (pintype "passive"))
    )
    (net (code "59") (name "Net-(RR2-Pad4)") (class "Default")
      (node (ref "RR2") (pin "4") (pinfunction "4_4") (pintype "passive"))
      (node (ref "RR3") (pin "12") (pinfunction "12_12") (pintype "passive"))
    )
    (net (code "60") (name "Net-(RR2-Pad5)") (class "Default")
      (node (ref "RR2") (pin "5") (pinfunction "5_5") (pintype "passive"))
      (node (ref "RR3") (pin "13") (pinfunction "13_13") (pintype "passive"))
    )
    (net (code "61") (name "Net-(RR2-Pad6)") (class "Default")
      (node (ref "RR2") (pin "6") (pinfunction "6_6") (pintype "passive"))
      (node (ref "RR3") (pin "14") (pinfunction "14_14") (pintype "passive"))
    )
    (net (code "62") (name "Net-(RR2-Pad7)") (class "Default")
      (node (ref "RR2") (pin "7") (pinfunction "7_7") (pintype "passive"))
      (node (ref "RR3") (pin "15") (pinfunction "15_15") (pintype "passive"))
    )
    (net (code "63") (name "Net-(RR2-Pad8)") (class "Default")
      (node (ref "RR2") (pin "8") (pinfunction "8_8") (pintype "passive"))
      (node (ref "RR3") (pin "16") (pinfunction "16_16") (pintype "passive"))
    )
    (net (code "64") (name "Net-(RR13-Pad9)") (class "Default")
      (node (ref "RR13") (pin "9") (pinfunction "9_9") (pintype "passive"))
      (node (ref "RR14") (pin "1") (pinfunction "1_1") (pintype "passive"))
    )
    (net (code "65") (name "Net-(RR13-Pad10)") (class "Default")
      (node (ref "RR13") (pin "10") (pinfunction "10_10") (pintype "passive"))
      (node (ref "RR14") (pin "2") (pinfunction "2_2") (pintype "passive"))
    )
    (net (code "66") (name "Net-(RR13-Pad11)") (class "Default")
      (node (ref "RR13") (pin "11") (pinfunction "11_11") (pintype "passive"))
      (node (ref "RR14") (pin "3") (pinfunction "3_3") (pintype "passive"))
    )
    (net (code "67") (name "Net-(RR13-Pad12)") (class "Default")
      (node (ref "RR13") (pin "12") (pinfunction "12_12") (pintype "passive"))
      (node (ref "RR14") (pin "4") (pinfunction "4_4") (pintype "passive"))
    )
    (net (code "68") (name "Net-(RR13-Pad13)") (class "Default")
      (node (ref "RR13") (pin "13") (pinfunction "13_13") (pintype "passive"))
      (node (ref "RR14") (pin "5") (pinfunction "5_5") (pintype "passive"))
    )
    (net (code "69") (name "Net-(RR13-Pad14)") (class "Default")
      (node (ref "RR13") (pin "14") (pinfunction "14_14") (pintype "passive"))
      (node (ref "RR14") (pin "6") (pinfunction "6_6") (pintype "passive"))
    )
    (net (code "70") (name "Net-(RR13-Pad15)") (class "Default")
      (node (ref "RR13") (pin "15") (pinfunction "15_15") (pintype "passive"))
      (node (ref "RR14") (pin "7") (pinfunction "7_7") (pintype "passive"))
    )
    (net (code "71") (name "Net-(RR13-Pad16)") (class "Default")
      (node (ref "RR13") (pin "16") (pinfunction "16_16") (pintype "passive"))
      (node (ref "RR14") (pin "8") (pinfunction "8_8") (pintype "passive"))
    )
    (net (code "72") (name "Net-(TP70-TP)") (class "Default")
      (node (ref "R128") (pin "1") (pinfunction "1_1") (pintype "passive"))
      (node (ref "RR4") (pin "1") (pinfunction "1_1") (pintype "passive"))
      (node (ref "TP70") (pin "1") (pinfunction "TP_1") (pintype "passive"))
    )
    (net (code "73") (name "Net-(TP71-TP)") (class "Default")
      (node (ref "R132") (pin "1") (pinfunction "1_1") (pintype "passive"))
      (node (ref "RR4") (pin "2") (pinfunction "2_2") (pintype "passive"))
      (node (ref "TP71") (pin "1") (pinfunction "TP_1") (pintype "passive"))
    )
    (net (code "74") (name "Net-(TP72-TP)") (class "Default")
      (node (ref "RR4") (pin "4") (pinfunction "4_4") (pintype "passive"))
      (node (ref "TP72") (pin "1") (pinfunction "TP_1") (pintype "passive"))
    )
    (net (code "75") (name "Net-(U25-A0)") (class "Default")
      (node (ref "R229") (pin "2") (pinfunction "2_2") (pintype "passive"))
      (node (ref "R230") (pin "1") (pinfunction "1_1") (pintype "passive"))
      (node (ref "U25") (pin "15") (pinfunction "A0_15") (pintype "input"))
    )
    (net (code "76") (name "Net-(U25-A1)") (class "Default")
      (node (ref "R231") (pin "2") (pinfunction "2_2") (pintype "passive"))
      (node (ref "R233") (pin "1") (pinfunction "1_1") (pintype "passive"))
      (node (ref "U25") (pin "16") (pinfunction "A1_16") (pintype "input"))
    )
    (net (code "77") (name "Net-(U25-A2)") (class "Default")
      (node (ref "R232") (pin "2") (pinfunction "2_2") (pintype "passive"))
      (node (ref "R234") (pin "1") (pinfunction "1_1") (pintype "passive"))
      (node (ref "U25") (pin "1") (pinfunction "A2_1") (pintype "input"))
    )
    (net (code "78") (name "Net-(U25-IO6)") (class "Default")
      (node (ref "R311") (pin "2") (pinfunction "2_2") (pintype "passive"))
      (node (ref "U25") (pin "9") (pinfunction "IO6_9") (pintype "bidirectional"))
    )
    (net (code "79") (name "Net-(U25-VDD)") (class "Default")
      (node (ref "C204") (pin "1") (pinfunction "1_1") (pintype "passive"))
      (node (ref "R230") (pin "2") (pinfunction "2_2") (pintype "passive"))
      (node (ref "R233") (pin "2") (pinfunction "2_2") (pintype "passive"))
      (node (ref "R234") (pin "2") (pinfunction "2_2") (pintype "passive"))
      (node (ref "R235") (pin "1") (pinfunction "1_1") (pintype "passive"))
      (node (ref "R236") (pin "1") (pinfunction "1_1") (pintype "passive"))
      (node (ref "U25") (pin "14") (pinfunction "VDD_14") (pintype "power_in"))
    )
    (net (code "80") (name "PERST_mPCIE") (class "Default")
      (node (ref "U25") (pin "8") (pinfunction "IO5_8") (pintype "bidirectional"))
    )
    (net (code "81") (name "PW_EN_LED") (class "Default")
      (node (ref "U25") (pin "10") (pinfunction "IO7_10") (pintype "bidirectional"))
    )
    (net (code "82") (name "PW_ON_3V3") (class "Default")
      (node (ref "MOD2") (pin "26") (pinfunction "PF5_26") (pintype "bidirectional"))
    )
    (net (code "83") (name "PW_ON_5V") (class "Default")
      (node (ref "MOD2") (pin "17") (pinfunction "PC9_17") (pintype "bidirectional"))
    )
    (net (code "84") (name "SEL_SWD") (class "Default")
      (node (ref "R297") (pin "1") (pinfunction "1_1") (pintype "passive"))
      (node (ref "R298") (pin "2") (pinfunction "2_2") (pintype "passive"))
      (node (ref "U29") (pin "10") (pinfunction "SEL_10") (pintype "input"))
    )
    (net (code "85") (name "SW_I2C_SCL_ON") (class "Default")
      (node (ref "MOD2") (pin "19") (pinfunction "PC11_19") (pintype "bidirectional"))
      (node (ref "Q18") (pin "3") (pinfunction "D2_3") (pintype "passive"))
      (node (ref "R284") (pin "1") (pinfunction "1_1") (pintype "passive"))
      (node (ref "R287") (pin "2") (pinfunction "2_2") (pintype "passive"))
      (node (ref "R288") (pin "1") (pinfunction "1_1") (pintype "passive"))
      (node (ref "R315") (pin "1") (pinfunction "1_1") (pintype "passive"))
      (node (ref "U30") (pin "6") (pinfunction "SCL_6") (pintype "open_collector"))
    )
    (net (code "86") (name "SW_I2C_SCL_ON_OFF") (class "Default")
      (node (ref "Q18") (pin "4") (pinfunction "S2_4") (pintype "passive"))
      (node (ref "R282") (pin "2") (pinfunction "2_2") (pintype "passive"))
      (node (ref "R287") (pin "1") (pinfunction "1_1") (pintype "passive"))
      (node (ref "U25") (pin "12") (pinfunction "SCL_12") (pintype "open_collector"))
    )
    (net (code "87") (name "SW_I2C_SDA_ON") (class "Default")
      (node (ref "MOD2") (pin "18") (pinfunction "PC10_18") (pintype "bidirectional"))
      (node (ref "Q18") (pin "6") (pinfunction "D1_6") (pintype "passive"))
      (node (ref "R285") (pin "2") (pinfunction "2_2") (pintype "passive"))
      (node (ref "R286") (pin "1") (pinfunction "1_1") (pintype "passive"))
      (node (ref "R289") (pin "2") (pinfunction "2_2") (pintype "passive"))
      (node (ref "R314") (pin "2") (pinfunction "2_2") (pintype "passive"))
      (node (ref "U30") (pin "7") (pinfunction "SDA_7") (pintype "open_collector"))
    )
    (net (code "88") (name "SW_I2C_SDA_ON_OFF") (class "Default")
      (node (ref "Q18") (pin "1") (pinfunction "S1_1") (pintype "passive"))
      (node (ref "R283") (pin "1") (pinfunction "1_1") (pintype "passive"))
      (node (ref "R286") (pin "2") (pinfunction "2_2") (pintype "passive"))
      (node (ref "U25") (pin "13") (pinfunction "SDA_13") (pintype "open_collector"))
    )
    (net (code "89") (name "W-DISABLE_mPCIE") (class "Default")
      (node (ref "U25") (pin "7") (pinfunction "IO4_7") (pintype "bidirectional"))
    )
    (net (code "90") (name "unconnected-(MOD2-PF4-Pad25)") (class "Default")
      (node (ref "MOD2") (pin "25") (pinfunction "PF4_25") (pintype "bidirectional"))
    )
    (net (code "91") (name "unconnected-(RR4-Pad3)") (class "Default")
      (node (ref "RR4") (pin "3") (pinfunction "3_3") (pintype "passive"))
    )
    (net (code "92") (name "unconnected-(RR4-Pad6)") (class "Default")
      (node (ref "RR4") (pin "6") (pinfunction "6_6") (pintype "passive"))
    )
    (net (code "93") (name "unconnected-(TVS6-NC4-Pad4)") (class "Default")
      (node (ref "TVS6") (pin "4") (pinfunction "NC4_4") (pintype "passive"))
    )
    (net (code "94") (name "unconnected-(TVS6-NC9-Pad9)") (class "Default")
      (node (ref "TVS6") (pin "9") (pinfunction "NC9_9") (pintype "passive"))
    )
    (net (code "95") (name "unconnected-(TVS7-NC4-Pad4)") (class "Default")
      (node (ref "TVS7") (pin "4") (pinfunction "NC4_4") (pintype "passive"))
    )
    (net (code "96") (name "unconnected-(TVS7-NC9-Pad9)") (class "Default")
      (node (ref "TVS7") (pin "9") (pinfunction "NC9_9") (pintype "passive"))
    )
    (net (code "97") (name "unconnected-(TVS18-IO5-Pad7)") (class "Default")
      (node (ref "TVS18") (pin "7") (pinfunction "IO5_7") (pintype "passive"))
    )
    (net (code "98") (name "unconnected-(TVS18-IO6-Pad8)") (class "Default")
      (node (ref "TVS18") (pin "8") (pinfunction "IO6_8") (pintype "passive"))
    )
    (net (code "99") (name "unconnected-(TVS18-NC4-Pad4)") (class "Default")
      (node (ref "TVS18") (pin "4") (pinfunction "NC4_4") (pintype "passive"))
    )
    (net (code "100") (name "unconnected-(TVS18-NC9-Pad9)") (class "Default")
      (node (ref "TVS18") (pin "9") (pinfunction "NC9_9") (pintype "passive"))
    )
    (net (code "101") (name "unconnected-(U25-IO0-Pad2)") (class "Default")
      (node (ref "U25") (pin "2") (pinfunction "IO0_2") (pintype "bidirectional"))
    )
    (net (code "102") (name "unconnected-(U25-IO1-Pad3)") (class "Default")
      (node (ref "U25") (pin "3") (pinfunction "IO1_3") (pintype "bidirectional"))
    )
    (net (code "103") (name "unconnected-(U25-IO2-Pad4)") (class "Default")
      (node (ref "U25") (pin "4") (pinfunction "IO2_4") (pintype "bidirectional"))
    )
    (net (code "104") (name "unconnected-(U25-~{INT}-Pad11)") (class "Default")
      (node (ref "U25") (pin "11") (pinfunction "~{INT}_11") (pintype "open_collector"))
    )
    (net (code "105") (name "unconnected-(U30-LED3-Pad4)") (class "Default")
      (node (ref "U30") (pin "4") (pinfunction "LED3_4") (pintype "open_collector"))
    )
  )
)
